# HackflightBrushed.net
KiCad netlist of a schematic drawn in EAGLE
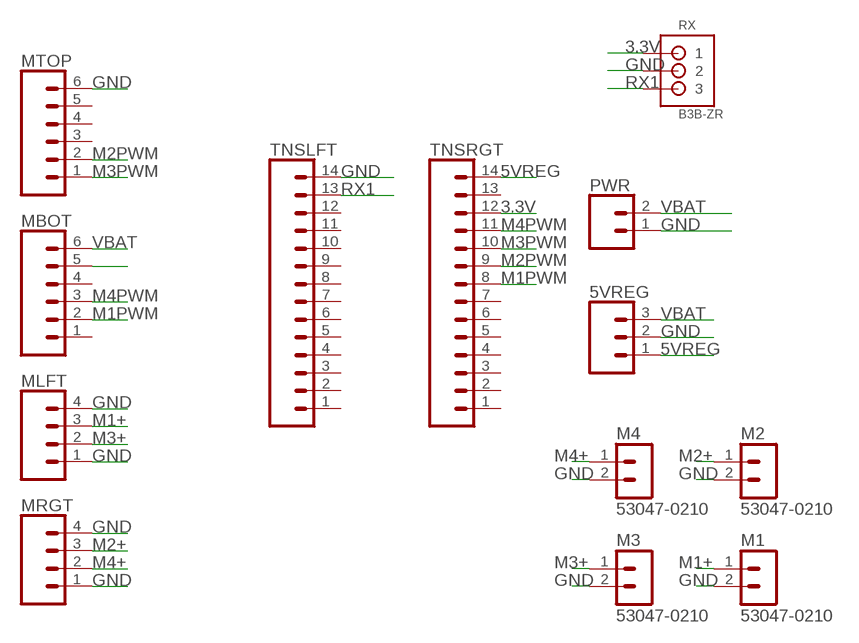
[diagram p0: schematic, sheet 1]

(export (version "E")
  (design (tool "Eeschema 10.0.6"))
  (components
    (comp (ref "5VREG")
      (value "CONN_03")
      (footprint "eagle-import:1X03")
      (libsource (lib "eagle-import") (part "CONN_03"))
    )
    (comp (ref "M1")
      (value "53047-0210")
      (footprint "eagle-import:53047-0210")
      (libsource (lib "eagle-import") (part "53047-0210"))
    )
    (comp (ref "M2")
      (value "53047-0210")
      (footprint "eagle-import:53047-0210")
      (libsource (lib "eagle-import") (part "53047-0210"))
    )
    (comp (ref "M3")
      (value "53047-0210")
      (footprint "eagle-import:53047-0210")
      (libsource (lib "eagle-import") (part "53047-0210"))
    )
    (comp (ref "M4")
      (value "53047-0210")
      (footprint "eagle-import:53047-0210")
      (libsource (lib "eagle-import") (part "53047-0210"))
    )
    (comp (ref "MBOT")
      (value "CONN_06NO_SILK_FEMALE_PTH")
      (footprint "eagle-import:1X06_NO_SILK")
      (libsource (lib "eagle-import") (part "CONN_06NO_SILK_FEMALE_PTH"))
    )
    (comp (ref "MLFT")
      (value "CONN_04")
      (footprint "eagle-import:1X04")
      (libsource (lib "eagle-import") (part "CONN_04"))
    )
    (comp (ref "MRGT")
      (value "CONN_04")
      (footprint "eagle-import:1X04")
      (libsource (lib "eagle-import") (part "CONN_04"))
    )
    (comp (ref "MTOP")
      (value "CONN_06NO_SILK_FEMALE_PTH")
      (footprint "eagle-import:1X06_NO_SILK")
      (libsource (lib "eagle-import") (part "CONN_06NO_SILK_FEMALE_PTH"))
    )
    (comp (ref "PWR")
      (value "CONN_02")
      (footprint "eagle-import:1X02")
      (libsource (lib "eagle-import") (part "CONN_02"))
    )
    (comp (ref "RX")
      (value "B3B-ZR")
      (footprint "eagle-import:B3B-ZR")
      (libsource (lib "eagle-import") (part "B3B-ZR"))
    )
    (comp (ref "TNSLFT")
      (value "CONN_14")
      (footprint "eagle-import:1X14")
      (libsource (lib "eagle-import") (part "CONN_14"))
    )
    (comp (ref "TNSRGT")
      (value "CONN_14")
      (footprint "eagle-import:1X14")
      (libsource (lib "eagle-import") (part "CONN_14"))
    )
  )
  (nets
    (net (code "1") (name "/3.3V") (class "Default")
      (node (ref "RX") (pin "1") (pinfunction "1_1") (pintype "bidirectional"))
      (node (ref "TNSRGT") (pin "12") (pinfunction "12_12") (pintype "passive"))
    )
    (net (code "2") (name "/5VREG") (class "Default")
      (node (ref "5VREG") (pin "1") (pinfunction "1_1") (pintype "passive"))
      (node (ref "TNSRGT") (pin "14") (pinfunction "14_14") (pintype "passive"))
    )
    (net (code "3") (name "/GND") (class "Default")
      (node (ref "5VREG") (pin "2") (pinfunction "2_2") (pintype "passive"))
      (node (ref "M1") (pin "2") (pinfunction "2_2") (pintype "passive"))
      (node (ref "M2") (pin "2") (pinfunction "2_2") (pintype "passive"))
      (node (ref "M3") (pin "2") (pinfunction "2_2") (pintype "passive"))
      (node (ref "M4") (pin "2") (pinfunction "2_2") (pintype "passive"))
      (node (ref "MLFT") (pin "1") (pinfunction "1_1") (pintype "passive"))
      (node (ref "MLFT") (pin "4") (pinfunction "4_4") (pintype "passive"))
      (node (ref "MRGT") (pin "1") (pinfunction "1_1") (pintype "passive"))
      (node (ref "MRGT") (pin "4") (pinfunction "4_4") (pintype "passive"))
      (node (ref "MTOP") (pin "6") (pinfunction "6_6") (pintype "passive"))
      (node (ref "PWR") (pin "1") (pinfunction "1_1") (pintype "passive"))
      (node (ref "RX") (pin "2") (pinfunction "2_2") (pintype "bidirectional"))
      (node (ref "TNSLFT") (pin "14") (pinfunction "14_14") (pintype "passive"))
    )
    (net (code "4") (name "/M1+") (class "Default")
      (node (ref "M1") (pin "1") (pinfunction "1_1") (pintype "passive"))
      (node (ref "MLFT") (pin "3") (pinfunction "3_3") (pintype "passive"))
    )
    (net (code "5") (name "/M1PWM") (class "Default")
      (node (ref "MBOT") (pin "2") (pinfunction "2_2") (pintype "passive"))
      (node (ref "TNSRGT") (pin "8") (pinfunction "8_8") (pintype "passive"))
    )
    (net (code "6") (name "/M2+") (class "Default")
      (node (ref "M2") (pin "1") (pinfunction "1_1") (pintype "passive"))
      (node (ref "MRGT") (pin "3") (pinfunction "3_3") (pintype "passive"))
    )
    (net (code "7") (name "/M2PWM") (class "Default")
      (node (ref "MTOP") (pin "2") (pinfunction "2_2") (pintype "passive"))
      (node (ref "TNSRGT") (pin "9") (pinfunction "9_9") (pintype "passive"))
    )
    (net (code "8") (name "/M3+") (class "Default")
      (node (ref "M3") (pin "1") (pinfunction "1_1") (pintype "passive"))
      (node (ref "MLFT") (pin "2") (pinfunction "2_2") (pintype "passive"))
    )
    (net (code "9") (name "/M3PWM") (class "Default")
      (node (ref "MTOP") (pin "1") (pinfunction "1_1") (pintype "passive"))
      (node (ref "TNSRGT") (pin "10") (pinfunction "10_10") (pintype "passive"))
    )
    (net (code "10") (name "/M4+") (class "Default")
      (node (ref "M4") (pin "1") (pinfunction "1_1") (pintype "passive"))
      (node (ref "MRGT") (pin "2") (pinfunction "2_2") (pintype "passive"))
    )
    (net (code "11") (name "/M4PWM") (class "Default")
      (node (ref "MBOT") (pin "3") (pinfunction "3_3") (pintype "passive"))
      (node (ref "TNSRGT") (pin "11") (pinfunction "11_11") (pintype "passive"))
    )
    (net (code "12") (name "/RX1") (class "Default")
      (node (ref "RX") (pin "3") (pinfunction "3_3") (pintype "bidirectional"))
      (node (ref "TNSLFT") (pin "13") (pinfunction "13_13") (pintype "passive"))
    )
    (net (code "13") (name "/VBAT") (class "Default")
      (node (ref "5VREG") (pin "3") (pinfunction "3_3") (pintype "passive"))
      (node (ref "MBOT") (pin "6") (pinfunction "6_6") (pintype "passive"))
      (node (ref "PWR") (pin "2") (pinfunction "2_2") (pintype "passive"))
    )
    (net (code "14") (name "unconnected-(MBOT-Pad1)") (class "Default")
      (node (ref "MBOT") (pin "1") (pinfunction "1_1") (pintype "passive"))
    )
    (net (code "15") (name "unconnected-(MBOT-Pad4)") (class "Default")
      (node (ref "MBOT") (pin "4") (pinfunction "4_4") (pintype "passive"))
    )
    (net (code "16") (name "unconnected-(MBOT-Pad5)") (class "Default")
      (node (ref "MBOT") (pin "5") (pinfunction "5_5") (pintype "passive"))
    )
    (net (code "17") (name "unconnected-(MTOP-Pad3)") (class "Default")
      (node (ref "MTOP") (pin "3") (pinfunction "3_3") (pintype "passive"))
    )
    (net (code "18") (name "unconnected-(MTOP-Pad4)") (class "Default")
      (node (ref "MTOP") (pin "4") (pinfunction "4_4") (pintype "passive"))
    )
    (net (code "19") (name "unconnected-(MTOP-Pad5)") (class "Default")
      (node (ref "MTOP") (pin "5") (pinfunction "5_5") (pintype "passive"))
    )
    (net (code "20") (name "unconnected-(TNSLFT-Pad1)") (class "Default")
      (node (ref "TNSLFT") (pin "1") (pinfunction "1_1") (pintype "passive"))
    )
    (net (code "21") (name "unconnected-(TNSLFT-Pad2)") (class "Default")
      (node (ref "TNSLFT") (pin "2") (pinfunction "2_2") (pintype "passive"))
    )
    (net (code "22") (name "unconnected-(TNSLFT-Pad3)") (class "Default")
      (node (ref "TNSLFT") (pin "3") (pinfunction "3_3") (pintype "passive"))
    )
    (net (code "23") (name "unconnected-(TNSLFT-Pad4)") (class "Default")
      (node (ref "TNSLFT") (pin "4") (pinfunction "4_4") (pintype "passive"))
    )
    (net (code "24") (name "unconnected-(TNSLFT-Pad5)") (class "Default")
      (node (ref "TNSLFT") (pin "5") (pinfunction "5_5") (pintype "passive"))
    )
    (net (code "25") (name "unconnected-(TNSLFT-Pad6)") (class "Default")
      (node (ref "TNSLFT") (pin "6") (pinfunction "6_6") (pintype "passive"))
    )
    (net (code "26") (name "unconnected-(TNSLFT-Pad7)") (class "Default")
      (node (ref "TNSLFT") (pin "7") (pinfunction "7_7") (pintype "passive"))
    )
    (net (code "27") (name "unconnected-(TNSLFT-Pad8)") (class "Default")
      (node (ref "TNSLFT") (pin "8") (pinfunction "8_8") (pintype "passive"))
    )
    (net (code "28") (name "unconnected-(TNSLFT-Pad9)") (class "Default")
      (node (ref "TNSLFT") (pin "9") (pinfunction "9_9") (pintype "passive"))
    )
    (net (code "29") (name "unconnected-(TNSLFT-Pad10)") (class "Default")
      (node (ref "TNSLFT") (pin "10") (pinfunction "10_10") (pintype "passive"))
    )
    (net (code "30") (name "unconnected-(TNSLFT-Pad11)") (class "Default")
      (node (ref "TNSLFT") (pin "11") (pinfunction "11_11") (pintype "passive"))
    )
    (net (code "31") (name "unconnected-(TNSLFT-Pad12)") (class "Default")
      (node (ref "TNSLFT") (pin "12") (pinfunction "12_12") (pintype "passive"))
    )
    (net (code "32") (name "unconnected-(TNSRGT-Pad1)") (class "Default")
      (node (ref "TNSRGT") (pin "1") (pinfunction "1_1") (pintype "passive"))
    )
    (net (code "33") (name "unconnected-(TNSRGT-Pad2)") (class "Default")
      (node (ref "TNSRGT") (pin "2") (pinfunction "2_2") (pintype "passive"))
    )
    (net (code "34") (name "unconnected-(TNSRGT-Pad3)") (class "Default")
      (node (ref "TNSRGT") (pin "3") (pinfunction "3_3") (pintype "passive"))
    )
    (net (code "35") (name "unconnected-(TNSRGT-Pad4)") (class "Default")
      (node (ref "TNSRGT") (pin "4") (pinfunction "4_4") (pintype "passive"))
    )
    (net (code "36") (name "unconnected-(TNSRGT-Pad5)") (class "Default")
      (node (ref "TNSRGT") (pin "5") (pinfunction "5_5") (pintype "passive"))
    )
    (net (code "37") (name "unconnected-(TNSRGT-Pad6)") (class "Default")
      (node (ref "TNSRGT") (pin "6") (pinfunction "6_6") (pintype "passive"))
    )
    (net (code "38") (name "unconnected-(TNSRGT-Pad7)") (class "Default")
      (node (ref "TNSRGT") (pin "7") (pinfunction "7_7") (pintype "passive"))
    )
    (net (code "39") (name "unconnected-(TNSRGT-Pad13)") (class "Default")
      (node (ref "TNSRGT") (pin "13") (pinfunction "13_13") (pintype "passive"))
    )
  )
)
